# led-test.net
KiCad netlist of a schematic drawn in EAGLE
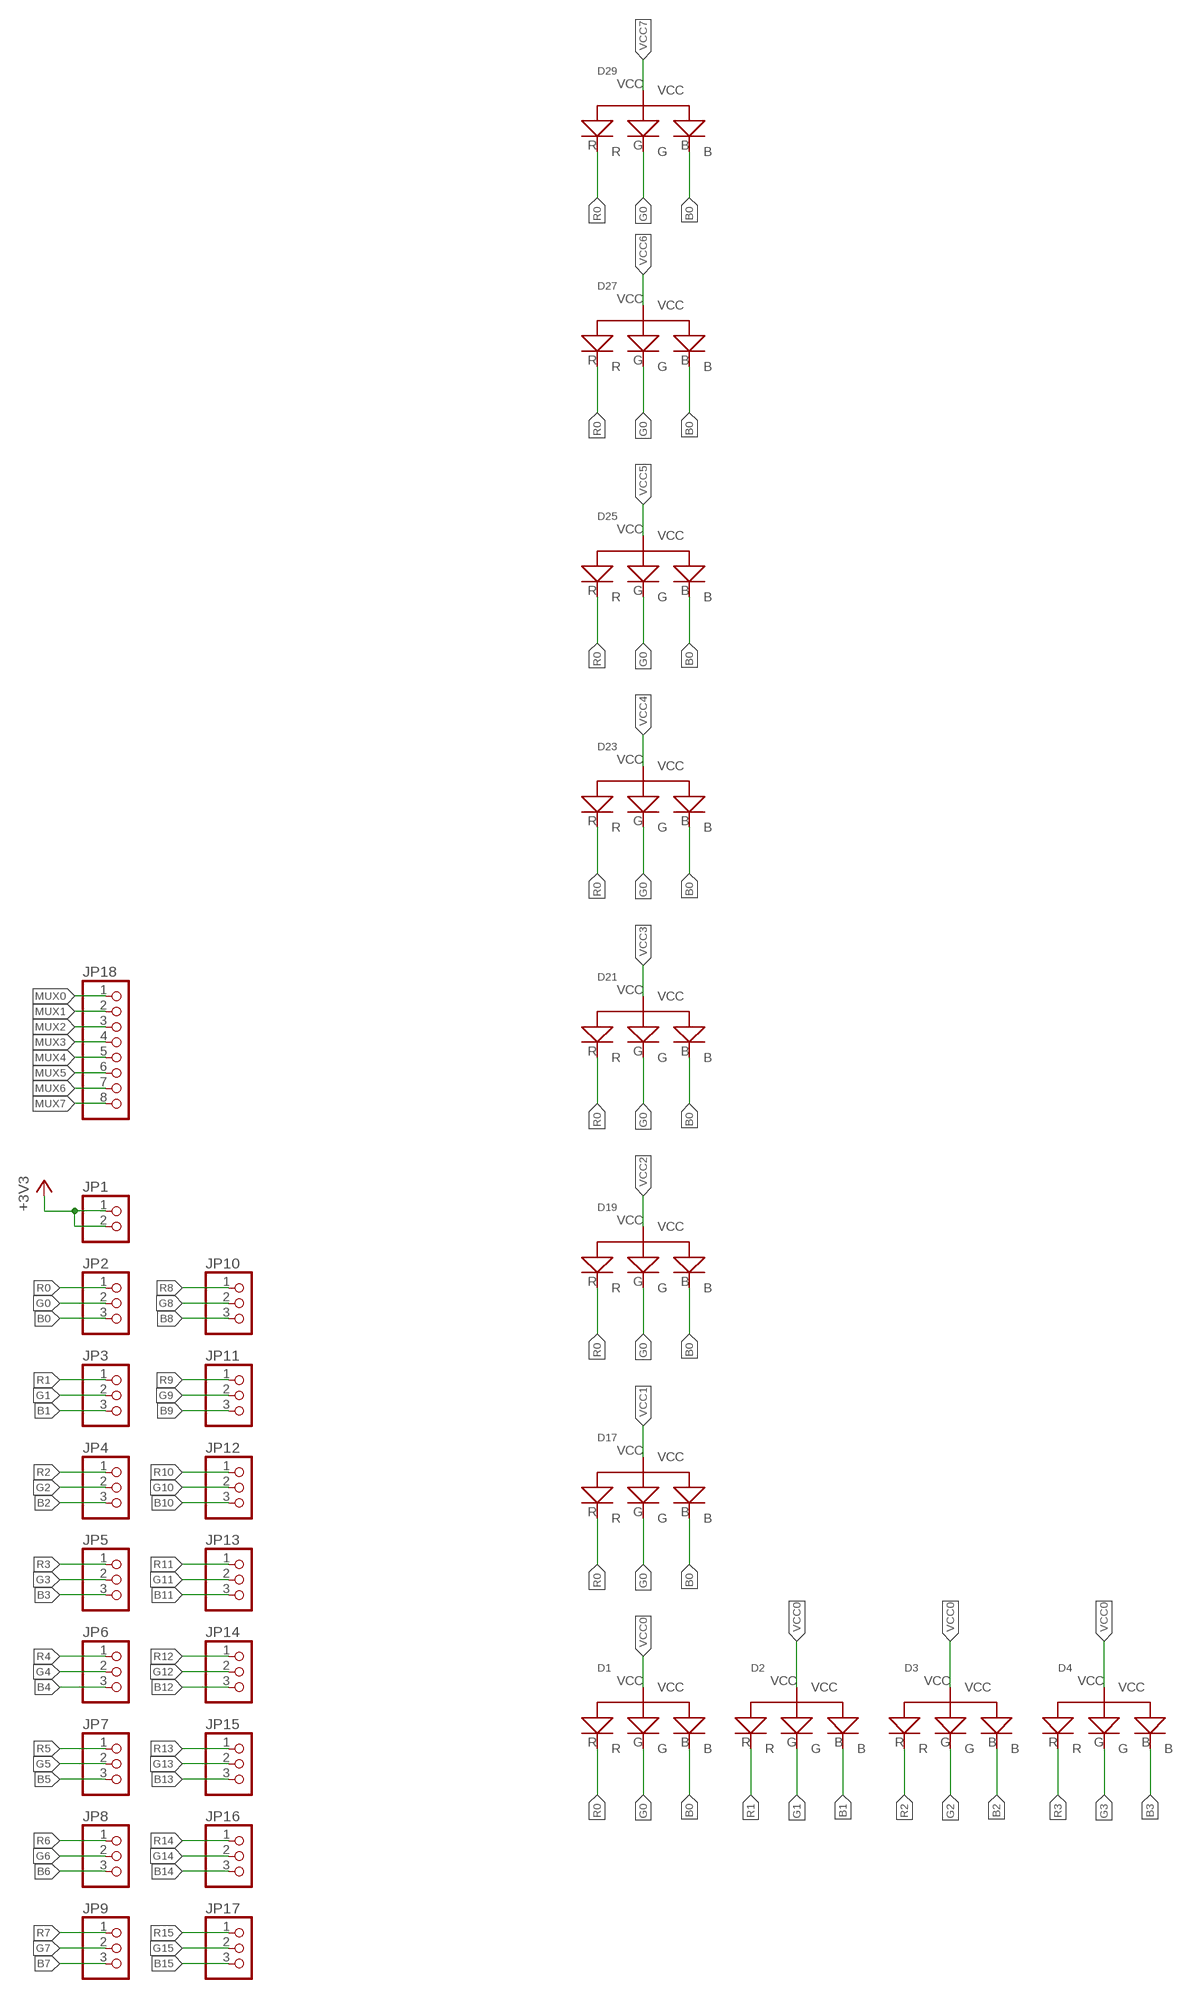
[diagram p0: schematic, sheet 1, part 1 of 2]
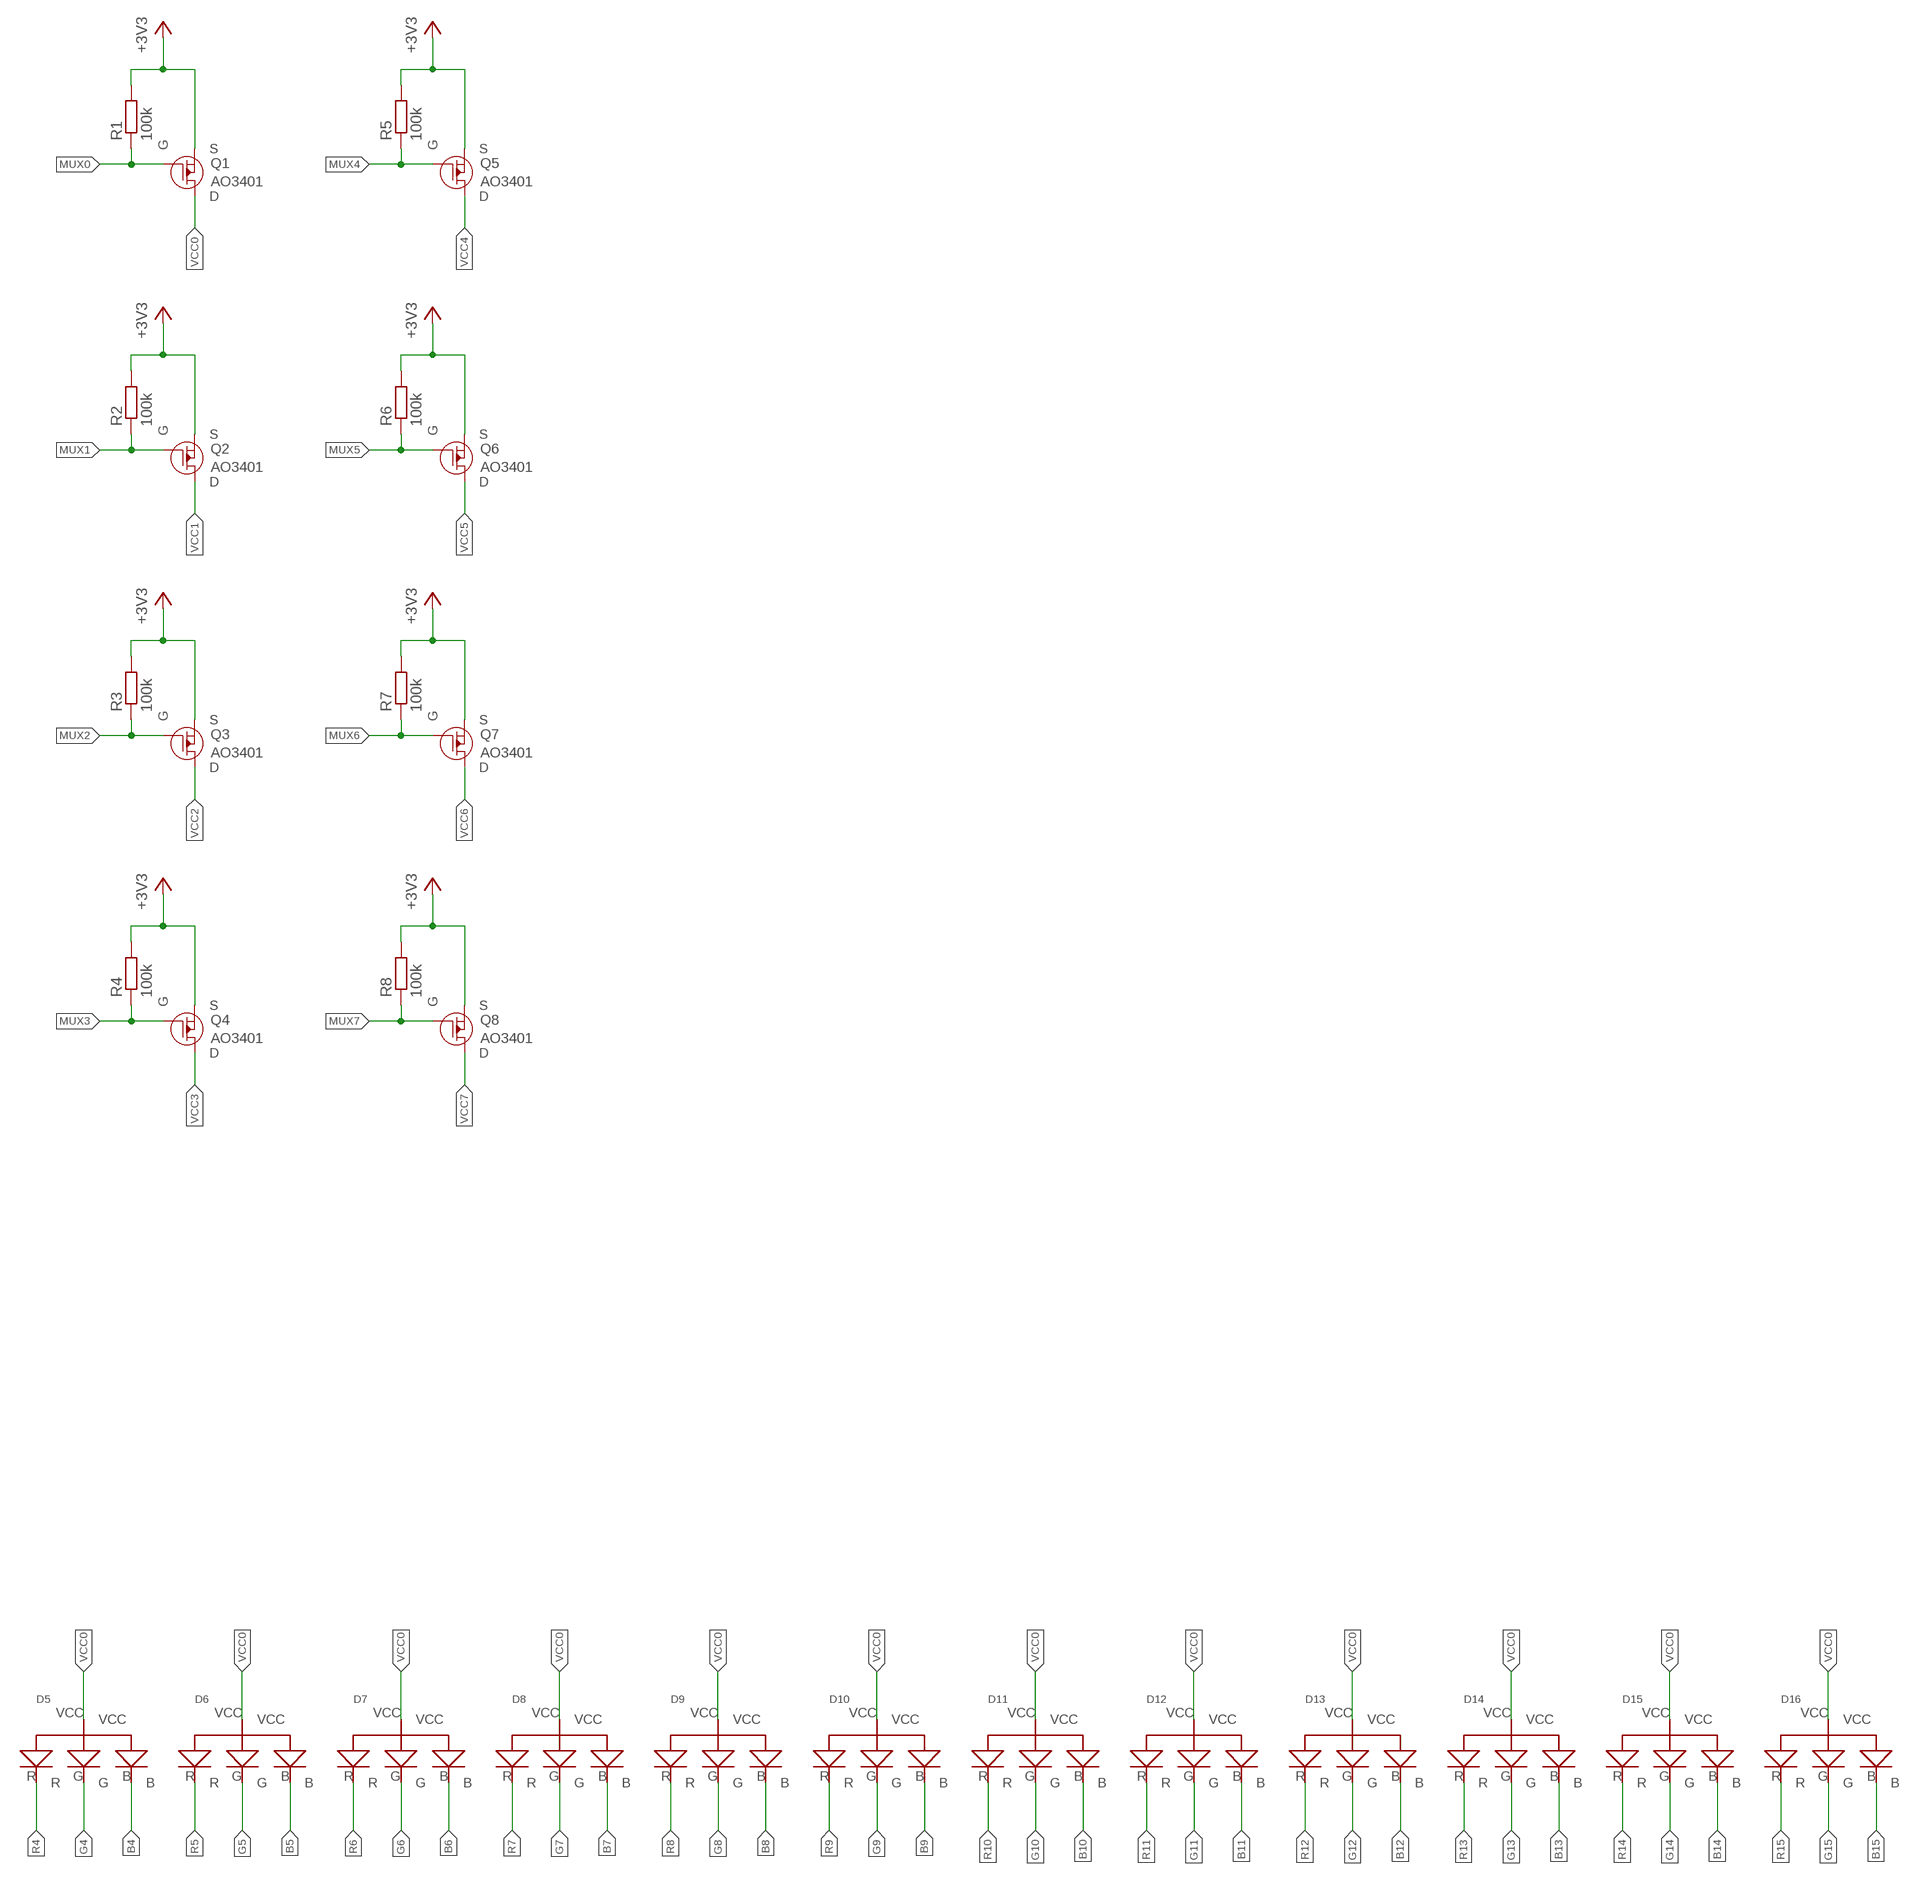
[diagram p1: schematic, sheet 1, part 2 of 2]

(export (version "E")
  (design (tool "Eeschema 10.0.6"))
  (components
    (comp (ref "D1")
      (value "LED3")
      (footprint "eagle-import:LED3")
      (libsource (lib "eagle-import") (part "LED3"))
    )
    (comp (ref "D2")
      (value "LED3")
      (footprint "eagle-import:LED3")
      (libsource (lib "eagle-import") (part "LED3"))
    )
    (comp (ref "D3")
      (value "LED3")
      (footprint "eagle-import:LED3")
      (libsource (lib "eagle-import") (part "LED3"))
    )
    (comp (ref "D4")
      (value "LED3")
      (footprint "eagle-import:LED3")
      (libsource (lib "eagle-import") (part "LED3"))
    )
    (comp (ref "D5")
      (value "LED3")
      (footprint "eagle-import:LED3")
      (libsource (lib "eagle-import") (part "LED3"))
    )
    (comp (ref "D6")
      (value "LED3")
      (footprint "eagle-import:LED3")
      (libsource (lib "eagle-import") (part "LED3"))
    )
    (comp (ref "D7")
      (value "LED3")
      (footprint "eagle-import:LED3")
      (libsource (lib "eagle-import") (part "LED3"))
    )
    (comp (ref "D8")
      (value "LED3")
      (footprint "eagle-import:LED3")
      (libsource (lib "eagle-import") (part "LED3"))
    )
    (comp (ref "D9")
      (value "LED3")
      (footprint "eagle-import:LED3")
      (libsource (lib "eagle-import") (part "LED3"))
    )
    (comp (ref "D10")
      (value "LED3")
      (footprint "eagle-import:LED3")
      (libsource (lib "eagle-import") (part "LED3"))
    )
    (comp (ref "D11")
      (value "LED3")
      (footprint "eagle-import:LED3")
      (libsource (lib "eagle-import") (part "LED3"))
    )
    (comp (ref "D12")
      (value "LED3")
      (footprint "eagle-import:LED3")
      (libsource (lib "eagle-import") (part "LED3"))
    )
    (comp (ref "D13")
      (value "LED3")
      (footprint "eagle-import:LED3")
      (libsource (lib "eagle-import") (part "LED3"))
    )
    (comp (ref "D14")
      (value "LED3")
      (footprint "eagle-import:LED3")
      (libsource (lib "eagle-import") (part "LED3"))
    )
    (comp (ref "D15")
      (value "LED3")
      (footprint "eagle-import:LED3")
      (libsource (lib "eagle-import") (part "LED3"))
    )
    (comp (ref "D16")
      (value "LED3")
      (footprint "eagle-import:LED3")
      (libsource (lib "eagle-import") (part "LED3"))
    )
    (comp (ref "D17")
      (value "LED3")
      (footprint "eagle-import:LED3")
      (libsource (lib "eagle-import") (part "LED3"))
    )
    (comp (ref "D19")
      (value "LED3")
      (footprint "eagle-import:LED3")
      (libsource (lib "eagle-import") (part "LED3"))
    )
    (comp (ref "D21")
      (value "LED3")
      (footprint "eagle-import:LED3")
      (libsource (lib "eagle-import") (part "LED3"))
    )
    (comp (ref "D23")
      (value "LED3")
      (footprint "eagle-import:LED3")
      (libsource (lib "eagle-import") (part "LED3"))
    )
    (comp (ref "D25")
      (value "LED3")
      (footprint "eagle-import:LED3")
      (libsource (lib "eagle-import") (part "LED3"))
    )
    (comp (ref "D27")
      (value "LED3")
      (footprint "eagle-import:LED3")
      (libsource (lib "eagle-import") (part "LED3"))
    )
    (comp (ref "D29")
      (value "LED3")
      (footprint "eagle-import:LED3")
      (libsource (lib "eagle-import") (part "LED3"))
    )
    (comp (ref "JP1")
      (value "PINHD-1X2")
      (footprint "eagle-import:1X02")
      (libsource (lib "eagle-import") (part "PINHD-1X2"))
    )
    (comp (ref "JP2")
      (value "PINHD-1X3")
      (footprint "eagle-import:1X03")
      (libsource (lib "eagle-import") (part "PINHD-1X3"))
    )
    (comp (ref "JP3")
      (value "PINHD-1X3")
      (footprint "eagle-import:1X03")
      (libsource (lib "eagle-import") (part "PINHD-1X3"))
    )
    (comp (ref "JP4")
      (value "PINHD-1X3")
      (footprint "eagle-import:1X03")
      (libsource (lib "eagle-import") (part "PINHD-1X3"))
    )
    (comp (ref "JP5")
      (value "PINHD-1X3")
      (footprint "eagle-import:1X03")
      (libsource (lib "eagle-import") (part "PINHD-1X3"))
    )
    (comp (ref "JP6")
      (value "PINHD-1X3")
      (footprint "eagle-import:1X03")
      (libsource (lib "eagle-import") (part "PINHD-1X3"))
    )
    (comp (ref "JP7")
      (value "PINHD-1X3")
      (footprint "eagle-import:1X03")
      (libsource (lib "eagle-import") (part "PINHD-1X3"))
    )
    (comp (ref "JP8")
      (value "PINHD-1X3")
      (footprint "eagle-import:1X03")
      (libsource (lib "eagle-import") (part "PINHD-1X3"))
    )
    (comp (ref "JP9")
      (value "PINHD-1X3")
      (footprint "eagle-import:1X03")
      (libsource (lib "eagle-import") (part "PINHD-1X3"))
    )
    (comp (ref "JP10")
      (value "PINHD-1X3")
      (footprint "eagle-import:1X03")
      (libsource (lib "eagle-import") (part "PINHD-1X3"))
    )
    (comp (ref "JP11")
      (value "PINHD-1X3")
      (footprint "eagle-import:1X03")
      (libsource (lib "eagle-import") (part "PINHD-1X3"))
    )
    (comp (ref "JP12")
      (value "PINHD-1X3")
      (footprint "eagle-import:1X03")
      (libsource (lib "eagle-import") (part "PINHD-1X3"))
    )
    (comp (ref "JP13")
      (value "PINHD-1X3")
      (footprint "eagle-import:1X03")
      (libsource (lib "eagle-import") (part "PINHD-1X3"))
    )
    (comp (ref "JP14")
      (value "PINHD-1X3")
      (footprint "eagle-import:1X03")
      (libsource (lib "eagle-import") (part "PINHD-1X3"))
    )
    (comp (ref "JP15")
      (value "PINHD-1X3")
      (footprint "eagle-import:1X03")
      (libsource (lib "eagle-import") (part "PINHD-1X3"))
    )
    (comp (ref "JP16")
      (value "PINHD-1X3")
      (footprint "eagle-import:1X03")
      (libsource (lib "eagle-import") (part "PINHD-1X3"))
    )
    (comp (ref "JP17")
      (value "PINHD-1X3")
      (footprint "eagle-import:1X03")
      (libsource (lib "eagle-import") (part "PINHD-1X3"))
    )
    (comp (ref "JP18")
      (value "PINHD-1X8")
      (footprint "eagle-import:1X08")
      (libsource (lib "eagle-import") (part "PINHD-1X8"))
    )
    (comp (ref "Q1")
      (value "AO3401")
      (footprint "eagle-import:SOT23-3")
      (libsource (lib "eagle-import") (part "AO3401"))
    )
    (comp (ref "Q2")
      (value "AO3401")
      (footprint "eagle-import:SOT23-3")
      (libsource (lib "eagle-import") (part "AO3401"))
    )
    (comp (ref "Q3")
      (value "AO3401")
      (footprint "eagle-import:SOT23-3")
      (libsource (lib "eagle-import") (part "AO3401"))
    )
    (comp (ref "Q4")
      (value "AO3401")
      (footprint "eagle-import:SOT23-3")
      (libsource (lib "eagle-import") (part "AO3401"))
    )
    (comp (ref "Q5")
      (value "AO3401")
      (footprint "eagle-import:SOT23-3")
      (libsource (lib "eagle-import") (part "AO3401"))
    )
    (comp (ref "Q6")
      (value "AO3401")
      (footprint "eagle-import:SOT23-3")
      (libsource (lib "eagle-import") (part "AO3401"))
    )
    (comp (ref "Q7")
      (value "AO3401")
      (footprint "eagle-import:SOT23-3")
      (libsource (lib "eagle-import") (part "AO3401"))
    )
    (comp (ref "Q8")
      (value "AO3401")
      (footprint "eagle-import:SOT23-3")
      (libsource (lib "eagle-import") (part "AO3401"))
    )
    (comp (ref "R1")
      (value "100k")
      (footprint "eagle-import:M0805")
      (libsource (lib "eagle-import") (part "R-EU_M0805"))
    )
    (comp (ref "R2")
      (value "100k")
      (footprint "eagle-import:M0805")
      (libsource (lib "eagle-import") (part "R-EU_M0805"))
    )
    (comp (ref "R3")
      (value "100k")
      (footprint "eagle-import:M0805")
      (libsource (lib "eagle-import") (part "R-EU_M0805"))
    )
    (comp (ref "R4")
      (value "100k")
      (footprint "eagle-import:M0805")
      (libsource (lib "eagle-import") (part "R-EU_M0805"))
    )
    (comp (ref "R5")
      (value "100k")
      (footprint "eagle-import:M0805")
      (libsource (lib "eagle-import") (part "R-EU_M0805"))
    )
    (comp (ref "R6")
      (value "100k")
      (footprint "eagle-import:M0805")
      (libsource (lib "eagle-import") (part "R-EU_M0805"))
    )
    (comp (ref "R7")
      (value "100k")
      (footprint "eagle-import:M0805")
      (libsource (lib "eagle-import") (part "R-EU_M0805"))
    )
    (comp (ref "R8")
      (value "100k")
      (footprint "eagle-import:M0805")
      (libsource (lib "eagle-import") (part "R-EU_M0805"))
    )
  )
  (nets
    (net (code "1") (name "+3V3") (class "Default")
      (node (ref "JP1") (pin "1") (pinfunction "1_1") (pintype "passive"))
      (node (ref "JP1") (pin "2") (pinfunction "2_2") (pintype "passive"))
      (node (ref "Q1") (pin "2") (pinfunction "S_2") (pintype "bidirectional"))
      (node (ref "Q2") (pin "2") (pinfunction "S_2") (pintype "bidirectional"))
      (node (ref "Q3") (pin "2") (pinfunction "S_2") (pintype "bidirectional"))
      (node (ref "Q4") (pin "2") (pinfunction "S_2") (pintype "bidirectional"))
      (node (ref "Q5") (pin "2") (pinfunction "S_2") (pintype "bidirectional"))
      (node (ref "Q6") (pin "2") (pinfunction "S_2") (pintype "bidirectional"))
      (node (ref "Q7") (pin "2") (pinfunction "S_2") (pintype "bidirectional"))
      (node (ref "Q8") (pin "2") (pinfunction "S_2") (pintype "bidirectional"))
      (node (ref "R1") (pin "2") (pinfunction "2_2") (pintype "passive"))
      (node (ref "R2") (pin "2") (pinfunction "2_2") (pintype "passive"))
      (node (ref "R3") (pin "2") (pinfunction "2_2") (pintype "passive"))
      (node (ref "R4") (pin "2") (pinfunction "2_2") (pintype "passive"))
      (node (ref "R5") (pin "2") (pinfunction "2_2") (pintype "passive"))
      (node (ref "R6") (pin "2") (pinfunction "2_2") (pintype "passive"))
      (node (ref "R7") (pin "2") (pinfunction "2_2") (pintype "passive"))
      (node (ref "R8") (pin "2") (pinfunction "2_2") (pintype "passive"))
    )
    (net (code "2") (name "B0") (class "Default")
      (node (ref "D1") (pin "B") (pinfunction "B_B") (pintype "bidirectional"))
      (node (ref "D17") (pin "B") (pinfunction "B_B") (pintype "bidirectional"))
      (node (ref "D19") (pin "B") (pinfunction "B_B") (pintype "bidirectional"))
      (node (ref "D21") (pin "B") (pinfunction "B_B") (pintype "bidirectional"))
      (node (ref "D23") (pin "B") (pinfunction "B_B") (pintype "bidirectional"))
      (node (ref "D25") (pin "B") (pinfunction "B_B") (pintype "bidirectional"))
      (node (ref "D27") (pin "B") (pinfunction "B_B") (pintype "bidirectional"))
      (node (ref "D29") (pin "B") (pinfunction "B_B") (pintype "bidirectional"))
      (node (ref "JP2") (pin "3") (pinfunction "3_3") (pintype "passive"))
    )
    (net (code "3") (name "B1") (class "Default")
      (node (ref "D2") (pin "B") (pinfunction "B_B") (pintype "bidirectional"))
      (node (ref "JP3") (pin "3") (pinfunction "3_3") (pintype "passive"))
    )
    (net (code "4") (name "B2") (class "Default")
      (node (ref "D3") (pin "B") (pinfunction "B_B") (pintype "bidirectional"))
      (node (ref "JP4") (pin "3") (pinfunction "3_3") (pintype "passive"))
    )
    (net (code "5") (name "B3") (class "Default")
      (node (ref "D4") (pin "B") (pinfunction "B_B") (pintype "bidirectional"))
      (node (ref "JP5") (pin "3") (pinfunction "3_3") (pintype "passive"))
    )
    (net (code "6") (name "B4") (class "Default")
      (node (ref "D5") (pin "B") (pinfunction "B_B") (pintype "bidirectional"))
      (node (ref "JP6") (pin "3") (pinfunction "3_3") (pintype "passive"))
    )
    (net (code "7") (name "B5") (class "Default")
      (node (ref "D6") (pin "B") (pinfunction "B_B") (pintype "bidirectional"))
      (node (ref "JP7") (pin "3") (pinfunction "3_3") (pintype "passive"))
    )
    (net (code "8") (name "B6") (class "Default")
      (node (ref "D7") (pin "B") (pinfunction "B_B") (pintype "bidirectional"))
      (node (ref "JP8") (pin "3") (pinfunction "3_3") (pintype "passive"))
    )
    (net (code "9") (name "B7") (class "Default")
      (node (ref "D8") (pin "B") (pinfunction "B_B") (pintype "bidirectional"))
      (node (ref "JP9") (pin "3") (pinfunction "3_3") (pintype "passive"))
    )
    (net (code "10") (name "B8") (class "Default")
      (node (ref "D9") (pin "B") (pinfunction "B_B") (pintype "bidirectional"))
      (node (ref "JP10") (pin "3") (pinfunction "3_3") (pintype "passive"))
    )
    (net (code "11") (name "B9") (class "Default")
      (node (ref "D10") (pin "B") (pinfunction "B_B") (pintype "bidirectional"))
      (node (ref "JP11") (pin "3") (pinfunction "3_3") (pintype "passive"))
    )
    (net (code "12") (name "B10") (class "Default")
      (node (ref "D11") (pin "B") (pinfunction "B_B") (pintype "bidirectional"))
      (node (ref "JP12") (pin "3") (pinfunction "3_3") (pintype "passive"))
    )
    (net (code "13") (name "B11") (class "Default")
      (node (ref "D12") (pin "B") (pinfunction "B_B") (pintype "bidirectional"))
      (node (ref "JP13") (pin "3") (pinfunction "3_3") (pintype "passive"))
    )
    (net (code "14") (name "B12") (class "Default")
      (node (ref "D13") (pin "B") (pinfunction "B_B") (pintype "bidirectional"))
      (node (ref "JP14") (pin "3") (pinfunction "3_3") (pintype "passive"))
    )
    (net (code "15") (name "B13") (class "Default")
      (node (ref "D14") (pin "B") (pinfunction "B_B") (pintype "bidirectional"))
      (node (ref "JP15") (pin "3") (pinfunction "3_3") (pintype "passive"))
    )
    (net (code "16") (name "B14") (class "Default")
      (node (ref "D15") (pin "B") (pinfunction "B_B") (pintype "bidirectional"))
      (node (ref "JP16") (pin "3") (pinfunction "3_3") (pintype "passive"))
    )
    (net (code "17") (name "B15") (class "Default")
      (node (ref "D16") (pin "B") (pinfunction "B_B") (pintype "bidirectional"))
      (node (ref "JP17") (pin "3") (pinfunction "3_3") (pintype "passive"))
    )
    (net (code "18") (name "G0") (class "Default")
      (node (ref "D1") (pin "G") (pinfunction "G_G") (pintype "bidirectional"))
      (node (ref "D17") (pin "G") (pinfunction "G_G") (pintype "bidirectional"))
      (node (ref "D19") (pin "G") (pinfunction "G_G") (pintype "bidirectional"))
      (node (ref "D21") (pin "G") (pinfunction "G_G") (pintype "bidirectional"))
      (node (ref "D23") (pin "G") (pinfunction "G_G") (pintype "bidirectional"))
      (node (ref "D25") (pin "G") (pinfunction "G_G") (pintype "bidirectional"))
      (node (ref "D27") (pin "G") (pinfunction "G_G") (pintype "bidirectional"))
      (node (ref "D29") (pin "G") (pinfunction "G_G") (pintype "bidirectional"))
      (node (ref "JP2") (pin "2") (pinfunction "2_2") (pintype "passive"))
    )
    (net (code "19") (name "G1") (class "Default")
      (node (ref "D2") (pin "G") (pinfunction "G_G") (pintype "bidirectional"))
      (node (ref "JP3") (pin "2") (pinfunction "2_2") (pintype "passive"))
    )
    (net (code "20") (name "G2") (class "Default")
      (node (ref "D3") (pin "G") (pinfunction "G_G") (pintype "bidirectional"))
      (node (ref "JP4") (pin "2") (pinfunction "2_2") (pintype "passive"))
    )
    (net (code "21") (name "G3") (class "Default")
      (node (ref "D4") (pin "G") (pinfunction "G_G") (pintype "bidirectional"))
      (node (ref "JP5") (pin "2") (pinfunction "2_2") (pintype "passive"))
    )
    (net (code "22") (name "G4") (class "Default")
      (node (ref "D5") (pin "G") (pinfunction "G_G") (pintype "bidirectional"))
      (node (ref "JP6") (pin "2") (pinfunction "2_2") (pintype "passive"))
    )
    (net (code "23") (name "G5") (class "Default")
      (node (ref "D6") (pin "G") (pinfunction "G_G") (pintype "bidirectional"))
      (node (ref "JP7") (pin "2") (pinfunction "2_2") (pintype "passive"))
    )
    (net (code "24") (name "G6") (class "Default")
      (node (ref "D7") (pin "G") (pinfunction "G_G") (pintype "bidirectional"))
      (node (ref "JP8") (pin "2") (pinfunction "2_2") (pintype "passive"))
    )
    (net (code "25") (name "G7") (class "Default")
      (node (ref "D8") (pin "G") (pinfunction "G_G") (pintype "bidirectional"))
      (node (ref "JP9") (pin "2") (pinfunction "2_2") (pintype "passive"))
    )
    (net (code "26") (name "G8") (class "Default")
      (node (ref "D9") (pin "G") (pinfunction "G_G") (pintype "bidirectional"))
      (node (ref "JP10") (pin "2") (pinfunction "2_2") (pintype "passive"))
    )
    (net (code "27") (name "G9") (class "Default")
      (node (ref "D10") (pin "G") (pinfunction "G_G") (pintype "bidirectional"))
      (node (ref "JP11") (pin "2") (pinfunction "2_2") (pintype "passive"))
    )
    (net (code "28") (name "G10") (class "Default")
      (node (ref "D11") (pin "G") (pinfunction "G_G") (pintype "bidirectional"))
      (node (ref "JP12") (pin "2") (pinfunction "2_2") (pintype "passive"))
    )
    (net (code "29") (name "G11") (class "Default")
      (node (ref "D12") (pin "G") (pinfunction "G_G") (pintype "bidirectional"))
      (node (ref "JP13") (pin "2") (pinfunction "2_2") (pintype "passive"))
    )
    (net (code "30") (name "G12") (class "Default")
      (node (ref "D13") (pin "G") (pinfunction "G_G") (pintype "bidirectional"))
      (node (ref "JP14") (pin "2") (pinfunction "2_2") (pintype "passive"))
    )
    (net (code "31") (name "G13") (class "Default")
      (node (ref "D14") (pin "G") (pinfunction "G_G") (pintype "bidirectional"))
      (node (ref "JP15") (pin "2") (pinfunction "2_2") (pintype "passive"))
    )
    (net (code "32") (name "G14") (class "Default")
      (node (ref "D15") (pin "G") (pinfunction "G_G") (pintype "bidirectional"))
      (node (ref "JP16") (pin "2") (pinfunction "2_2") (pintype "passive"))
    )
    (net (code "33") (name "G15") (class "Default")
      (node (ref "D16") (pin "G") (pinfunction "G_G") (pintype "bidirectional"))
      (node (ref "JP17") (pin "2") (pinfunction "2_2") (pintype "passive"))
    )
    (net (code "34") (name "MUX0") (class "Default")
      (node (ref "JP18") (pin "1") (pinfunction "1_1") (pintype "passive"))
      (node (ref "Q1") (pin "1") (pinfunction "G_1") (pintype "bidirectional"))
      (node (ref "R1") (pin "1") (pinfunction "1_1") (pintype "passive"))
    )
    (net (code "35") (name "MUX1") (class "Default")
      (node (ref "JP18") (pin "2") (pinfunction "2_2") (pintype "passive"))
      (node (ref "Q2") (pin "1") (pinfunction "G_1") (pintype "bidirectional"))
      (node (ref "R2") (pin "1") (pinfunction "1_1") (pintype "passive"))
    )
    (net (code "36") (name "MUX2") (class "Default")
      (node (ref "JP18") (pin "3") (pinfunction "3_3") (pintype "passive"))
      (node (ref "Q3") (pin "1") (pinfunction "G_1") (pintype "bidirectional"))
      (node (ref "R3") (pin "1") (pinfunction "1_1") (pintype "passive"))
    )
    (net (code "37") (name "MUX3") (class "Default")
      (node (ref "JP18") (pin "4") (pinfunction "4_4") (pintype "passive"))
      (node (ref "Q4") (pin "1") (pinfunction "G_1") (pintype "bidirectional"))
      (node (ref "R4") (pin "1") (pinfunction "1_1") (pintype "passive"))
    )
    (net (code "38") (name "MUX4") (class "Default")
      (node (ref "JP18") (pin "5") (pinfunction "5_5") (pintype "passive"))
      (node (ref "Q5") (pin "1") (pinfunction "G_1") (pintype "bidirectional"))
      (node (ref "R5") (pin "1") (pinfunction "1_1") (pintype "passive"))
    )
    (net (code "39") (name "MUX5") (class "Default")
      (node (ref "JP18") (pin "6") (pinfunction "6_6") (pintype "passive"))
      (node (ref "Q6") (pin "1") (pinfunction "G_1") (pintype "bidirectional"))
      (node (ref "R6") (pin "1") (pinfunction "1_1") (pintype "passive"))
    )
    (net (code "40") (name "MUX6") (class "Default")
      (node (ref "JP18") (pin "7") (pinfunction "7_7") (pintype "passive"))
      (node (ref "Q7") (pin "1") (pinfunction "G_1") (pintype "bidirectional"))
      (node (ref "R7") (pin "1") (pinfunction "1_1") (pintype "passive"))
    )
    (net (code "41") (name "MUX7") (class "Default")
      (node (ref "JP18") (pin "8") (pinfunction "8_8") (pintype "passive"))
      (node (ref "Q8") (pin "1") (pinfunction "G_1") (pintype "bidirectional"))
      (node (ref "R8") (pin "1") (pinfunction "1_1") (pintype "passive"))
    )
    (net (code "42") (name "R0") (class "Default")
      (node (ref "D1") (pin "R") (pinfunction "R_R") (pintype "bidirectional"))
      (node (ref "D17") (pin "R") (pinfunction "R_R") (pintype "bidirectional"))
      (node (ref "D19") (pin "R") (pinfunction "R_R") (pintype "bidirectional"))
      (node (ref "D21") (pin "R") (pinfunction "R_R") (pintype "bidirectional"))
      (node (ref "D23") (pin "R") (pinfunction "R_R") (pintype "bidirectional"))
      (node (ref "D25") (pin "R") (pinfunction "R_R") (pintype "bidirectional"))
      (node (ref "D27") (pin "R") (pinfunction "R_R") (pintype "bidirectional"))
      (node (ref "D29") (pin "R") (pinfunction "R_R") (pintype "bidirectional"))
      (node (ref "JP2") (pin "1") (pinfunction "1_1") (pintype "passive"))
    )
    (net (code "43") (name "R1") (class "Default")
      (node (ref "D2") (pin "R") (pinfunction "R_R") (pintype "bidirectional"))
      (node (ref "JP3") (pin "1") (pinfunction "1_1") (pintype "passive"))
    )
    (net (code "44") (name "R2") (class "Default")
      (node (ref "D3") (pin "R") (pinfunction "R_R") (pintype "bidirectional"))
      (node (ref "JP4") (pin "1") (pinfunction "1_1") (pintype "passive"))
    )
    (net (code "45") (name "R3") (class "Default")
      (node (ref "D4") (pin "R") (pinfunction "R_R") (pintype "bidirectional"))
      (node (ref "JP5") (pin "1") (pinfunction "1_1") (pintype "passive"))
    )
    (net (code "46") (name "R4") (class "Default")
      (node (ref "D5") (pin "R") (pinfunction "R_R") (pintype "bidirectional"))
      (node (ref "JP6") (pin "1") (pinfunction "1_1") (pintype "passive"))
    )
    (net (code "47") (name "R5") (class "Default")
      (node (ref "D6") (pin "R") (pinfunction "R_R") (pintype "bidirectional"))
      (node (ref "JP7") (pin "1") (pinfunction "1_1") (pintype "passive"))
    )
    (net (code "48") (name "R6") (class "Default")
      (node (ref "D7") (pin "R") (pinfunction "R_R") (pintype "bidirectional"))
      (node (ref "JP8") (pin "1") (pinfunction "1_1") (pintype "passive"))
    )
    (net (code "49") (name "R7") (class "Default")
      (node (ref "D8") (pin "R") (pinfunction "R_R") (pintype "bidirectional"))
      (node (ref "JP9") (pin "1") (pinfunction "1_1") (pintype "passive"))
    )
    (net (code "50") (name "R8") (class "Default")
      (node (ref "D9") (pin "R") (pinfunction "R_R") (pintype "bidirectional"))
      (node (ref "JP10") (pin "1") (pinfunction "1_1") (pintype "passive"))
    )
    (net (code "51") (name "R9") (class "Default")
      (node (ref "D10") (pin "R") (pinfunction "R_R") (pintype "bidirectional"))
      (node (ref "JP11") (pin "1") (pinfunction "1_1") (pintype "passive"))
    )
    (net (code "52") (name "R10") (class "Default")
      (node (ref "D11") (pin "R") (pinfunction "R_R") (pintype "bidirectional"))
      (node (ref "JP12") (pin "1") (pinfunction "1_1") (pintype "passive"))
    )
    (net (code "53") (name "R11") (class "Default")
      (node (ref "D12") (pin "R") (pinfunction "R_R") (pintype "bidirectional"))
      (node (ref "JP13") (pin "1") (pinfunction "1_1") (pintype "passive"))
    )
    (net (code "54") (name "R12") (class "Default")
      (node (ref "D13") (pin "R") (pinfunction "R_R") (pintype "bidirectional"))
      (node (ref "JP14") (pin "1") (pinfunction "1_1") (pintype "passive"))
    )
    (net (code "55") (name "R13") (class "Default")
      (node (ref "D14") (pin "R") (pinfunction "R_R") (pintype "bidirectional"))
      (node (ref "JP15") (pin "1") (pinfunction "1_1") (pintype "passive"))
    )
    (net (code "56") (name "R14") (class "Default")
      (node (ref "D15") (pin "R") (pinfunction "R_R") (pintype "bidirectional"))
      (node (ref "JP16") (pin "1") (pinfunction "1_1") (pintype "passive"))
    )
    (net (code "57") (name "R15") (class "Default")
      (node (ref "D16") (pin "R") (pinfunction "R_R") (pintype "bidirectional"))
      (node (ref "JP17") (pin "1") (pinfunction "1_1") (pintype "passive"))
    )
    (net (code "58") (name "VCC0") (class "Default")
      (node (ref "D1") (pin "VCC") (pinfunction "VCC_VCC") (pintype "bidirectional"))
      (node (ref "D10") (pin "VCC") (pinfunction "VCC_VCC") (pintype "bidirectional"))
      (node (ref "D11") (pin "VCC") (pinfunction "VCC_VCC") (pintype "bidirectional"))
      (node (ref "D12") (pin "VCC") (pinfunction "VCC_VCC") (pintype "bidirectional"))
      (node (ref "D13") (pin "VCC") (pinfunction "VCC_VCC") (pintype "bidirectional"))
      (node (ref "D14") (pin "VCC") (pinfunction "VCC_VCC") (pintype "bidirectional"))
      (node (ref "D15") (pin "VCC") (pinfunction "VCC_VCC") (pintype "bidirectional"))
      (node (ref "D16") (pin "VCC") (pinfunction "VCC_VCC") (pintype "bidirectional"))
      (node (ref "D2") (pin "VCC") (pinfunction "VCC_VCC") (pintype "bidirectional"))
      (node (ref "D3") (pin "VCC") (pinfunction "VCC_VCC") (pintype "bidirectional"))
      (node (ref "D4") (pin "VCC") (pinfunction "VCC_VCC") (pintype "bidirectional"))
      (node (ref "D5") (pin "VCC") (pinfunction "VCC_VCC") (pintype "bidirectional"))
      (node (ref "D6") (pin "VCC") (pinfunction "VCC_VCC") (pintype "bidirectional"))
      (node (ref "D7") (pin "VCC") (pinfunction "VCC_VCC") (pintype "bidirectional"))
      (node (ref "D8") (pin "VCC") (pinfunction "VCC_VCC") (pintype "bidirectional"))
      (node (ref "D9") (pin "VCC") (pinfunction "VCC_VCC") (pintype "bidirectional"))
      (node (ref "Q1") (pin "3") (pinfunction "D_3") (pintype "bidirectional"))
    )
    (net (code "59") (name "VCC1") (class "Default")
      (node (ref "D17") (pin "VCC") (pinfunction "VCC_VCC") (pintype "bidirectional"))
      (node (ref "Q2") (pin "3") (pinfunction "D_3") (pintype "bidirectional"))
    )
    (net (code "60") (name "VCC2") (class "Default")
      (node (ref "D19") (pin "VCC") (pinfunction "VCC_VCC") (pintype "bidirectional"))
      (node (ref "Q3") (pin "3") (pinfunction "D_3") (pintype "bidirectional"))
    )
    (net (code "61") (name "VCC3") (class "Default")
      (node (ref "D21") (pin "VCC") (pinfunction "VCC_VCC") (pintype "bidirectional"))
      (node (ref "Q4") (pin "3") (pinfunction "D_3") (pintype "bidirectional"))
    )
    (net (code "62") (name "VCC4") (class "Default")
      (node (ref "D23") (pin "VCC") (pinfunction "VCC_VCC") (pintype "bidirectional"))
      (node (ref "Q5") (pin "3") (pinfunction "D_3") (pintype "bidirectional"))
    )
    (net (code "63") (name "VCC5") (class "Default")
      (node (ref "D25") (pin "VCC") (pinfunction "VCC_VCC") (pintype "bidirectional"))
      (node (ref "Q6") (pin "3") (pinfunction "D_3") (pintype "bidirectional"))
    )
    (net (code "64") (name "VCC6") (class "Default")
      (node (ref "D27") (pin "VCC") (pinfunction "VCC_VCC") (pintype "bidirectional"))
      (node (ref "Q7") (pin "3") (pinfunction "D_3") (pintype "bidirectional"))
    )
    (net (code "65") (name "VCC7") (class "Default")
      (node (ref "D29") (pin "VCC") (pinfunction "VCC_VCC") (pintype "bidirectional"))
      (node (ref "Q8") (pin "3") (pinfunction "D_3") (pintype "bidirectional"))
    )
  )
)
